# QCopterMV-CameraExp_Sch.net
KiCad netlist of a schematic drawn in Altium Designer
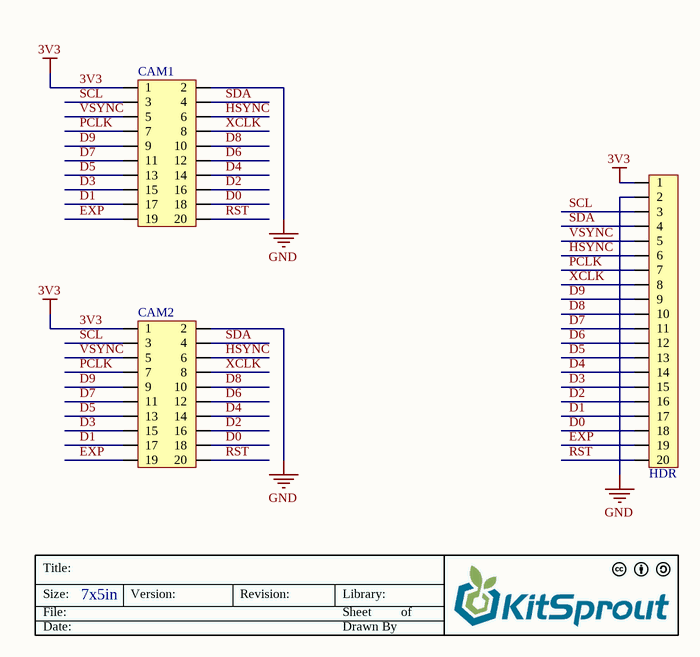
[diagram p0: QCopterMV-CameraExp_Sch.SchDoc]

(export (version "E")
  (design (tool "Eeschema 10.0.6"))
  (components
    (comp (ref "CAM1")
      (value "HDR2x10_2.54")
      (footprint "PCB_ConnectorHDR:HDR2X10_2.54_180F")
      (description "Header")
      (libsource (lib "SCH_ConnectorHDR") (part "HDR2x10_2.54"))
    )
    (comp (ref "CAM2")
      (value "HDR2x10_2.54")
      (footprint "PCB_ConnectorHDR:HDR2X10_2.54_180F")
      (description "Header")
      (libsource (lib "SCH_ConnectorHDR") (part "HDR2x10_2.54"))
    )
    (comp (ref "HDR")
      (value "HDR1x20_1.27")
      (footprint "PCB_ConnectorHDR:HDR1X20_1.27_180")
      (description "Header")
      (libsource (lib "SCH_ConnectorHDR") (part "HDR1x20_1.27"))
    )
  )
  (nets
    (net (code "1") (name "/D0") (class "Default")
      (node (ref "CAM1") (pin "18") (pinfunction "18_18") (pintype "passive"))
      (node (ref "CAM2") (pin "18") (pinfunction "18_18") (pintype "passive"))
      (node (ref "HDR") (pin "18") (pinfunction "18_18") (pintype "passive"))
    )
    (net (code "2") (name "/D1") (class "Default")
      (node (ref "CAM1") (pin "17") (pinfunction "17_17") (pintype "passive"))
      (node (ref "CAM2") (pin "17") (pinfunction "17_17") (pintype "passive"))
      (node (ref "HDR") (pin "17") (pinfunction "17_17") (pintype "passive"))
    )
    (net (code "3") (name "/D2") (class "Default")
      (node (ref "CAM1") (pin "16") (pinfunction "16_16") (pintype "passive"))
      (node (ref "CAM2") (pin "16") (pinfunction "16_16") (pintype "passive"))
      (node (ref "HDR") (pin "16") (pinfunction "16_16") (pintype "passive"))
    )
    (net (code "4") (name "/D3") (class "Default")
      (node (ref "CAM1") (pin "15") (pinfunction "15_15") (pintype "passive"))
      (node (ref "CAM2") (pin "15") (pinfunction "15_15") (pintype "passive"))
      (node (ref "HDR") (pin "15") (pinfunction "15_15") (pintype "passive"))
    )
    (net (code "5") (name "/D4") (class "Default")
      (node (ref "CAM1") (pin "14") (pinfunction "14_14") (pintype "passive"))
      (node (ref "CAM2") (pin "14") (pinfunction "14_14") (pintype "passive"))
      (node (ref "HDR") (pin "14") (pinfunction "14_14") (pintype "passive"))
    )
    (net (code "6") (name "/D5") (class "Default")
      (node (ref "CAM1") (pin "13") (pinfunction "13_13") (pintype "passive"))
      (node (ref "CAM2") (pin "13") (pinfunction "13_13") (pintype "passive"))
      (node (ref "HDR") (pin "13") (pinfunction "13_13") (pintype "passive"))
    )
    (net (code "7") (name "/D6") (class "Default")
      (node (ref "CAM1") (pin "12") (pinfunction "12_12") (pintype "passive"))
      (node (ref "CAM2") (pin "12") (pinfunction "12_12") (pintype "passive"))
      (node (ref "HDR") (pin "12") (pinfunction "12_12") (pintype "passive"))
    )
    (net (code "8") (name "/D7") (class "Default")
      (node (ref "CAM1") (pin "11") (pinfunction "11_11") (pintype "passive"))
      (node (ref "CAM2") (pin "11") (pinfunction "11_11") (pintype "passive"))
      (node (ref "HDR") (pin "11") (pinfunction "11_11") (pintype "passive"))
    )
    (net (code "9") (name "/D8") (class "Default")
      (node (ref "CAM1") (pin "10") (pinfunction "10_10") (pintype "passive"))
      (node (ref "CAM2") (pin "10") (pinfunction "10_10") (pintype "passive"))
      (node (ref "HDR") (pin "10") (pinfunction "10_10") (pintype "passive"))
    )
    (net (code "10") (name "/D9") (class "Default")
      (node (ref "CAM1") (pin "9") (pinfunction "9_9") (pintype "passive"))
      (node (ref "CAM2") (pin "9") (pinfunction "9_9") (pintype "passive"))
      (node (ref "HDR") (pin "9") (pinfunction "9_9") (pintype "passive"))
    )
    (net (code "11") (name "/EXP") (class "Default")
      (node (ref "CAM1") (pin "19") (pinfunction "19_19") (pintype "passive"))
      (node (ref "CAM2") (pin "19") (pinfunction "19_19") (pintype "passive"))
      (node (ref "HDR") (pin "19") (pinfunction "19_19") (pintype "passive"))
    )
    (net (code "12") (name "/HSYNC") (class "Default")
      (node (ref "CAM1") (pin "6") (pinfunction "6_6") (pintype "passive"))
      (node (ref "CAM2") (pin "6") (pinfunction "6_6") (pintype "passive"))
      (node (ref "HDR") (pin "6") (pinfunction "6_6") (pintype "passive"))
    )
    (net (code "13") (name "/PCLK") (class "Default")
      (node (ref "CAM1") (pin "7") (pinfunction "7_7") (pintype "passive"))
      (node (ref "CAM2") (pin "7") (pinfunction "7_7") (pintype "passive"))
      (node (ref "HDR") (pin "7") (pinfunction "7_7") (pintype "passive"))
    )
    (net (code "14") (name "/RST") (class "Default")
      (node (ref "CAM1") (pin "20") (pinfunction "20_20") (pintype "passive"))
      (node (ref "CAM2") (pin "20") (pinfunction "20_20") (pintype "passive"))
      (node (ref "HDR") (pin "20") (pinfunction "20_20") (pintype "passive"))
    )
    (net (code "15") (name "/SCL") (class "Default")
      (node (ref "CAM1") (pin "3") (pinfunction "3_3") (pintype "passive"))
      (node (ref "CAM2") (pin "3") (pinfunction "3_3") (pintype "passive"))
      (node (ref "HDR") (pin "3") (pinfunction "3_3") (pintype "passive"))
    )
    (net (code "16") (name "/SDA") (class "Default")
      (node (ref "CAM1") (pin "4") (pinfunction "4_4") (pintype "passive"))
      (node (ref "CAM2") (pin "4") (pinfunction "4_4") (pintype "passive"))
      (node (ref "HDR") (pin "4") (pinfunction "4_4") (pintype "passive"))
    )
    (net (code "17") (name "/VSYNC") (class "Default")
      (node (ref "CAM1") (pin "5") (pinfunction "5_5") (pintype "passive"))
      (node (ref "CAM2") (pin "5") (pinfunction "5_5") (pintype "passive"))
      (node (ref "HDR") (pin "5") (pinfunction "5_5") (pintype "passive"))
    )
    (net (code "18") (name "/XCLK") (class "Default")
      (node (ref "CAM1") (pin "8") (pinfunction "8_8") (pintype "passive"))
      (node (ref "CAM2") (pin "8") (pinfunction "8_8") (pintype "passive"))
      (node (ref "HDR") (pin "8") (pinfunction "8_8") (pintype "passive"))
    )
    (net (code "19") (name "3V3") (class "Default")
      (node (ref "CAM1") (pin "1") (pinfunction "1_1") (pintype "passive"))
      (node (ref "CAM2") (pin "1") (pinfunction "1_1") (pintype "passive"))
      (node (ref "HDR") (pin "1") (pinfunction "1_1") (pintype "passive"))
    )
    (net (code "20") (name "GND") (class "Default")
      (node (ref "CAM1") (pin "2") (pinfunction "2_2") (pintype "passive"))
      (node (ref "CAM2") (pin "2") (pinfunction "2_2") (pintype "passive"))
      (node (ref "HDR") (pin "2") (pinfunction "2_2") (pintype "passive"))
    )
  )
)
